# ESP_SCH.net
KiCad netlist of a schematic drawn in Altium Designer
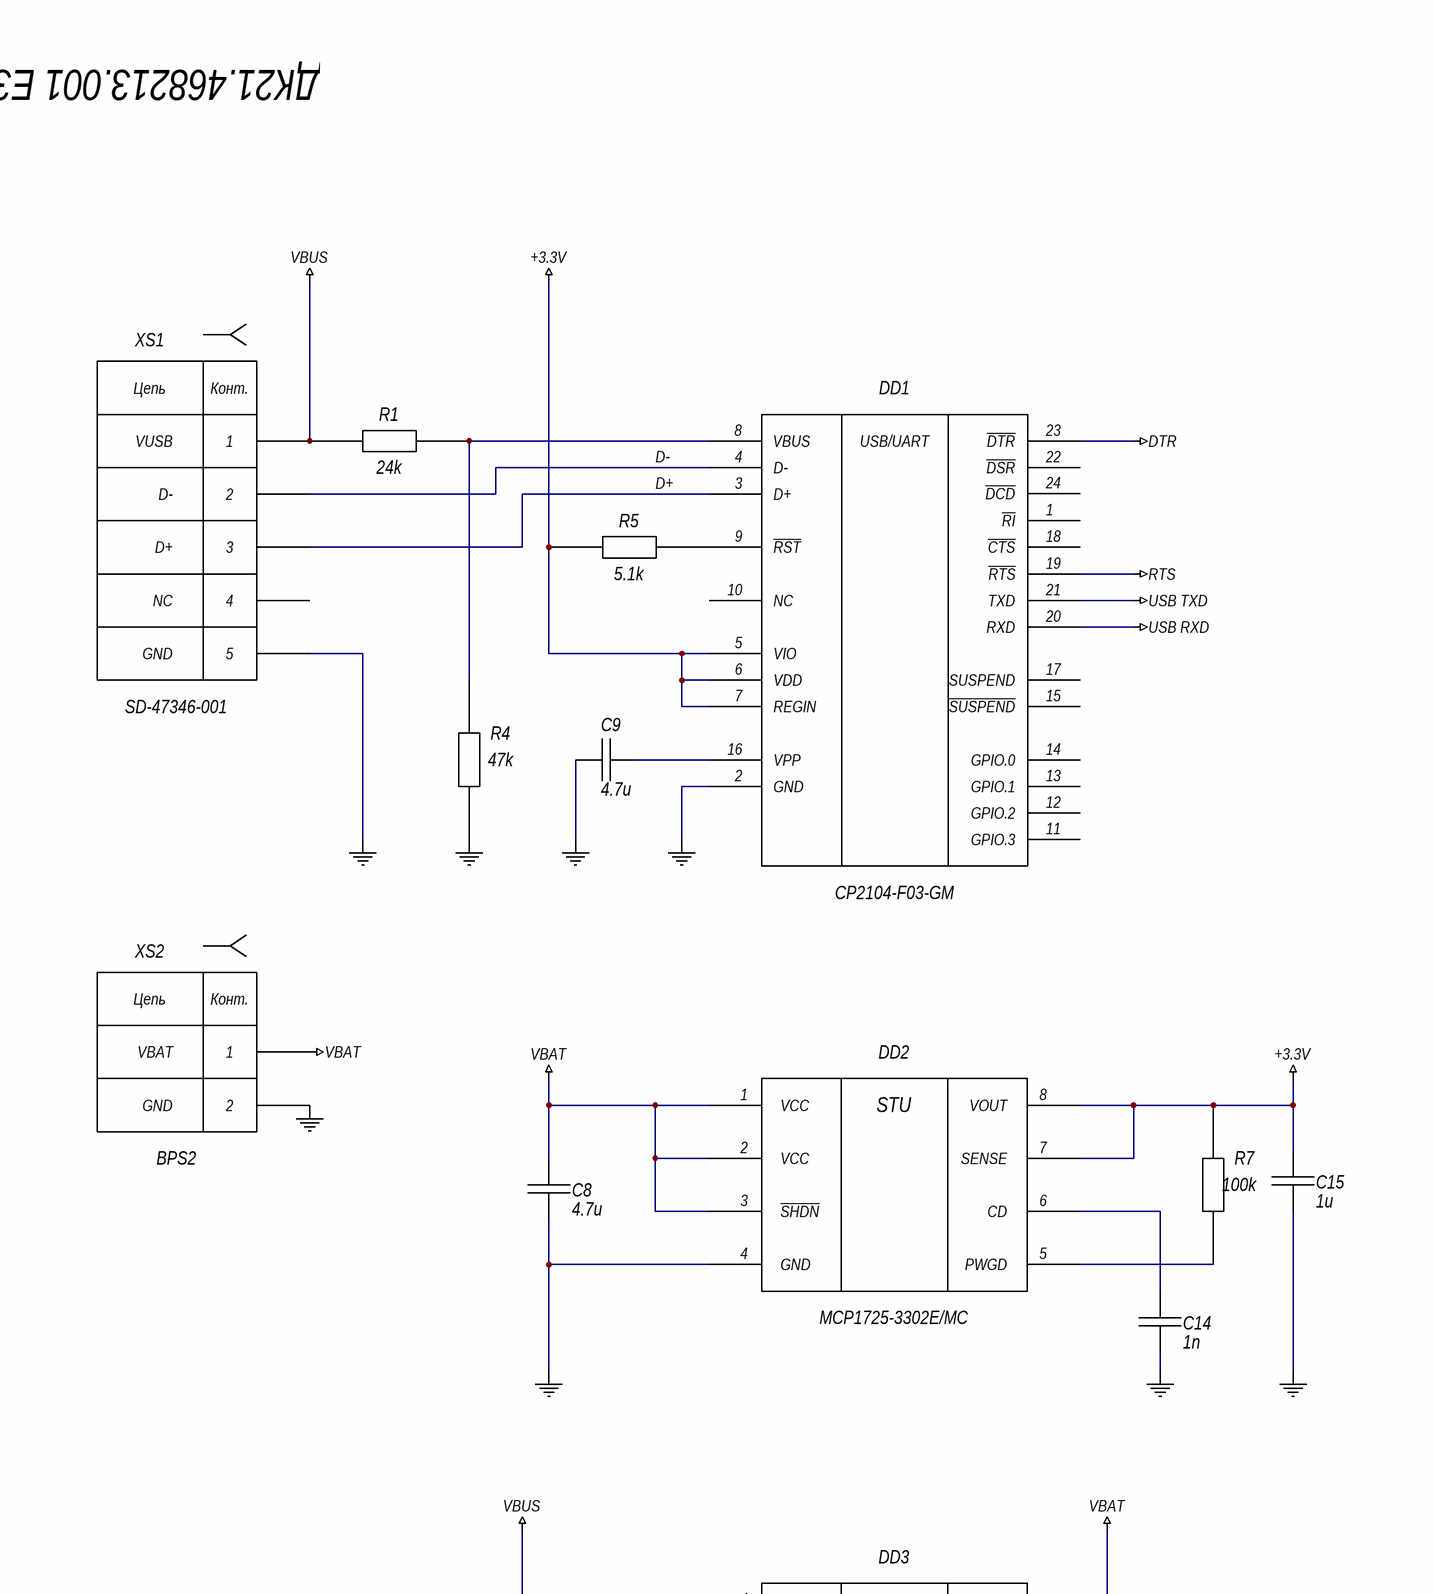
[diagram p0: ESP_SCH.SchDoc, top left]
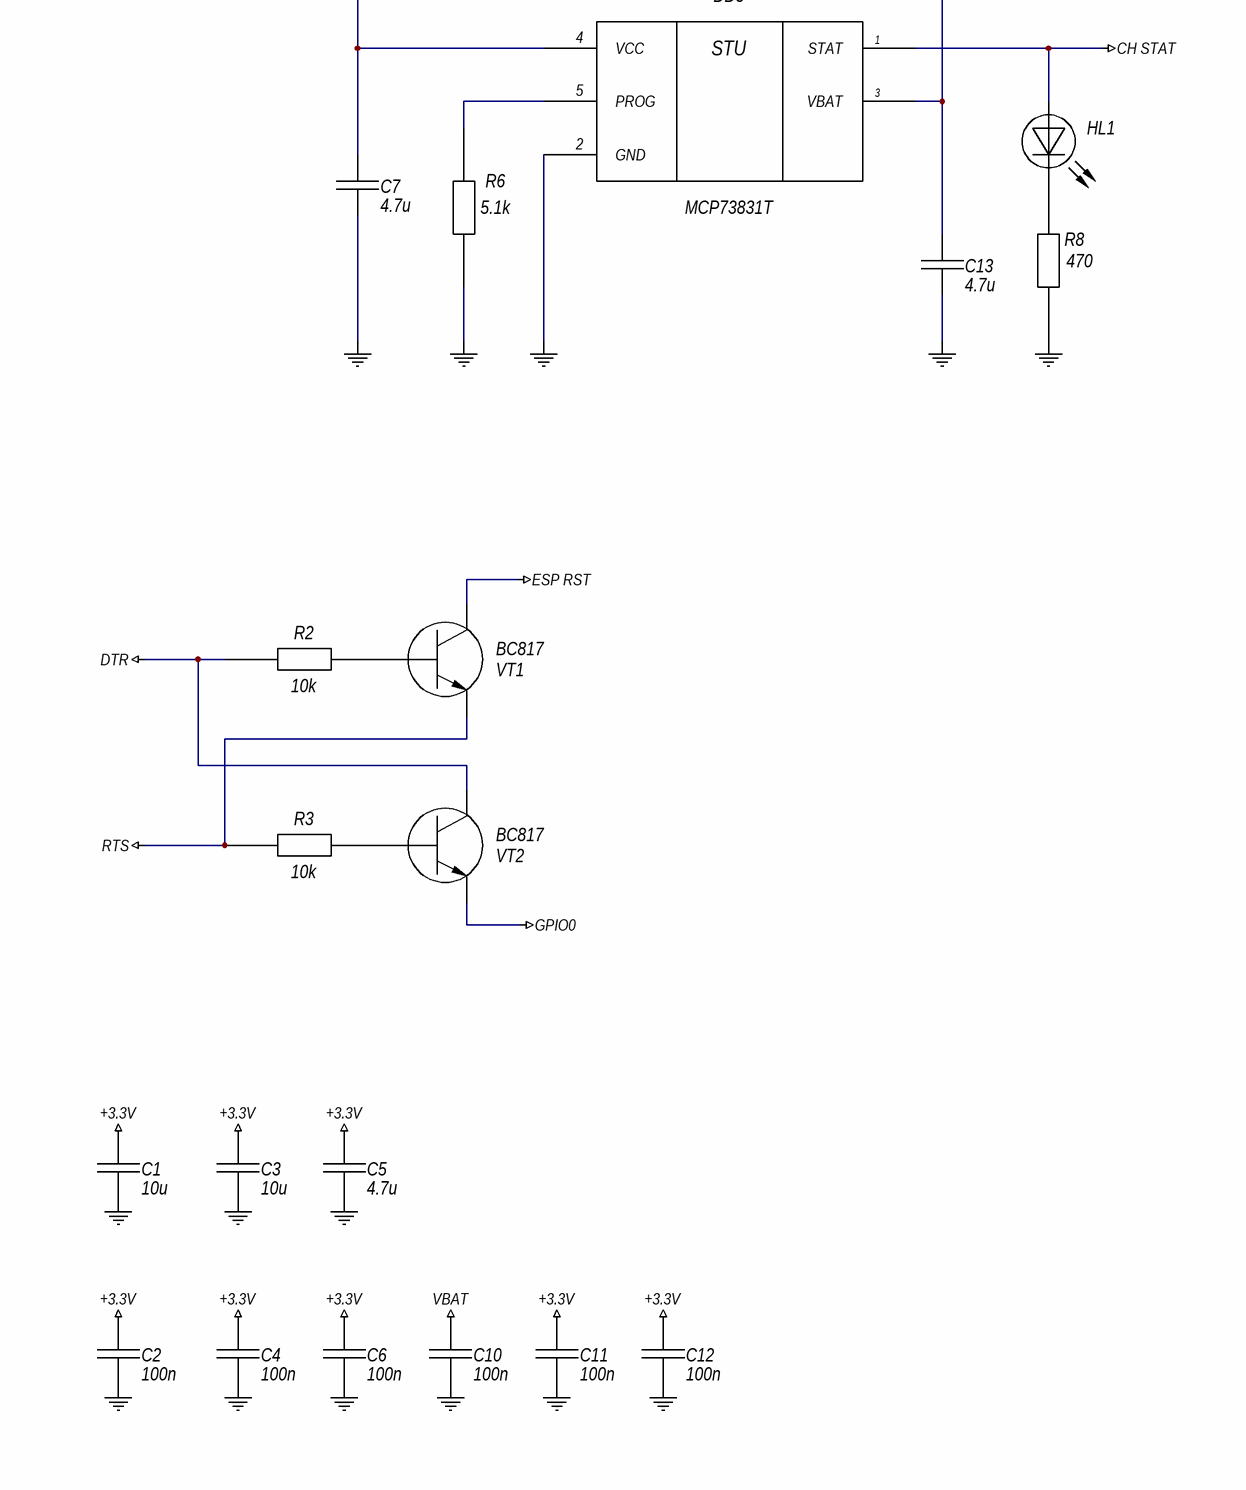
[diagram p1: ESP_SCH.SchDoc, bottom left]
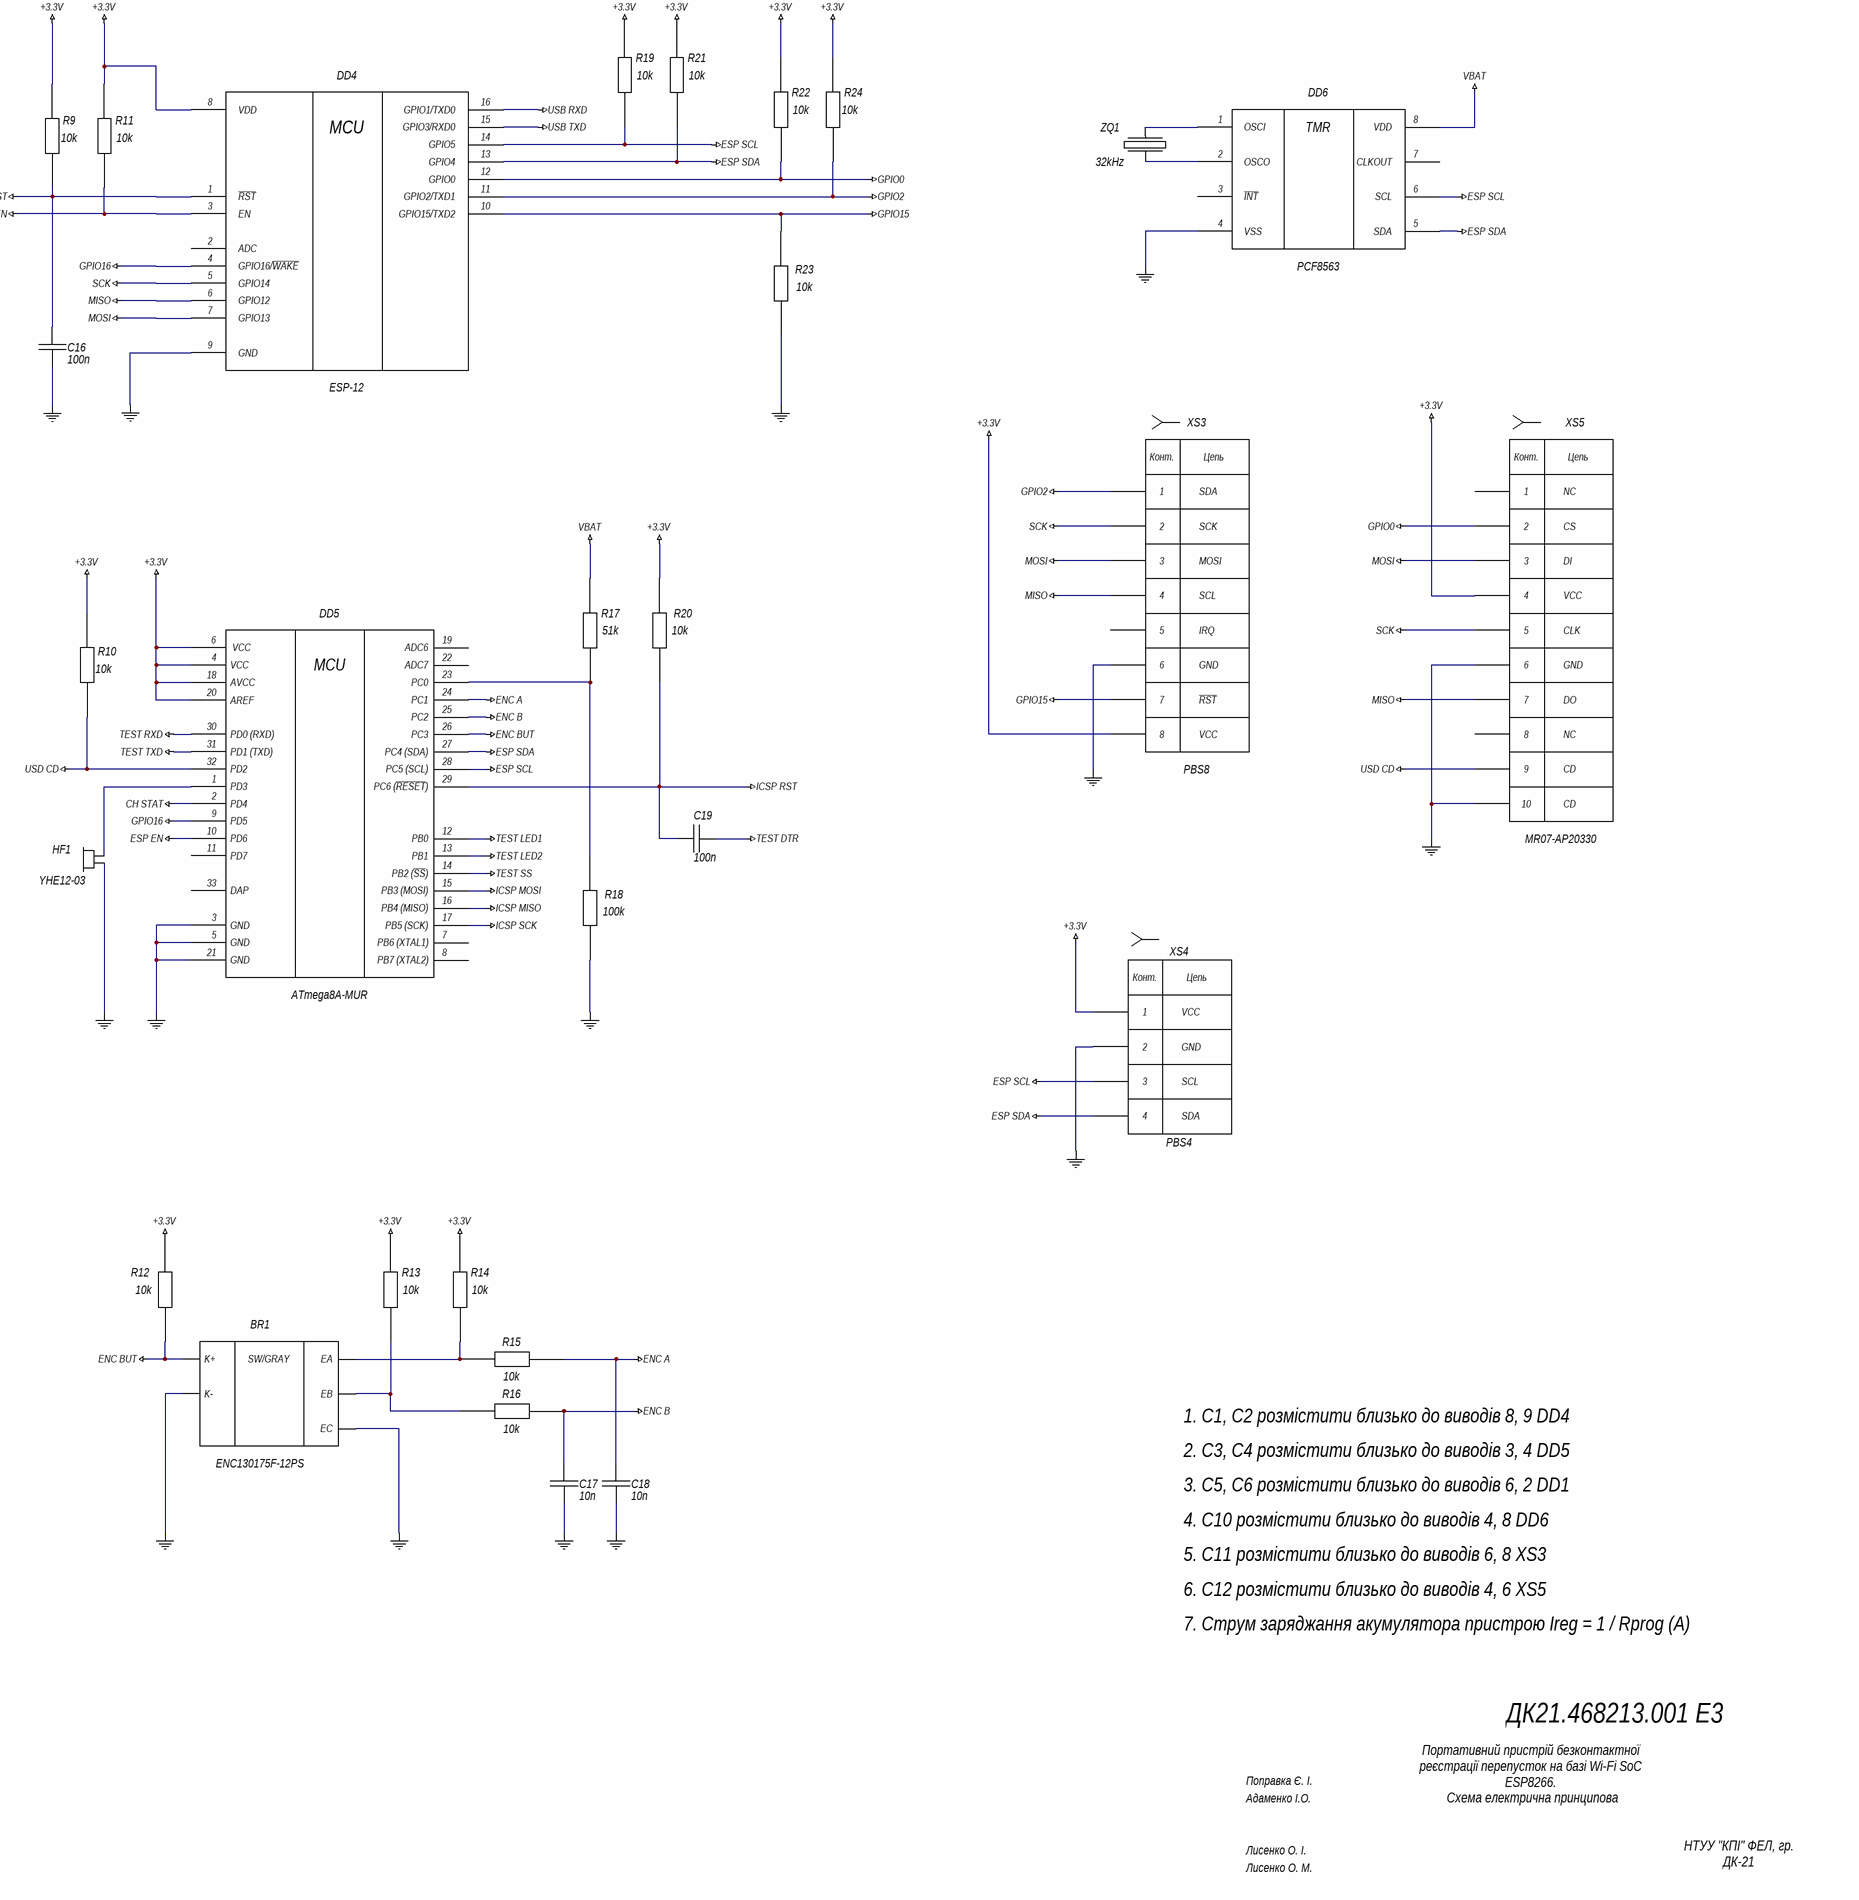
[diagram p2: ESP_SCH.SchDoc, bottom right]

(export (version "E")
  (design (tool "Eeschema 10.0.6"))
  (components
    (comp (ref "BR1")
      (value "ENC130175F-12PS")
      (footprint "ENCODER_LED_2")
      (libsource (lib "Symbols GOST") (part "ENC130175F-12PS"))
    )
    (comp (ref "C1")
      (value "10u")
      (footprint "RES0603")
      (description "Chip capasitor")
      (fields (field (name "PART NUMBER") "GRJ32ER71H475KE11") (field (name "VOLTAGE") "50V"))
      (libsource (lib "Symbols GOST") (part "C0805"))
    )
    (comp (ref "C2")
      (value "100n")
      (footprint "RES0603")
      (description "Chip capasitor")
      (fields (field (name "PART NUMBER") "GRJ32ER71H475KE11") (field (name "VOLTAGE") "50V"))
      (libsource (lib "Symbols GOST") (part "C0805"))
    )
    (comp (ref "C3")
      (value "10u")
      (footprint "RES0603")
      (description "Chip capasitor")
      (fields (field (name "PART NUMBER") "GRJ32ER71H475KE11") (field (name "VOLTAGE") "50V"))
      (libsource (lib "Symbols GOST") (part "C0805"))
    )
    (comp (ref "C4")
      (value "100n")
      (footprint "RES0603")
      (description "Chip capasitor")
      (fields (field (name "PART NUMBER") "GRJ32ER71H475KE11") (field (name "VOLTAGE") "50V"))
      (libsource (lib "Symbols GOST") (part "C0805"))
    )
    (comp (ref "C5")
      (value "4.7u")
      (footprint "RES0603")
      (description "Chip capasitor")
      (fields (field (name "PART NUMBER") "GRJ32ER71H475KE11") (field (name "VOLTAGE") "50V"))
      (libsource (lib "Symbols GOST") (part "C0805"))
    )
    (comp (ref "C6")
      (value "100n")
      (footprint "RES0603")
      (description "Chip capasitor")
      (fields (field (name "PART NUMBER") "GRJ32ER71H475KE11") (field (name "VOLTAGE") "50V"))
      (libsource (lib "Symbols GOST") (part "C0805"))
    )
    (comp (ref "C7")
      (value "4.7u")
      (footprint "RES0603")
      (description "Chip capasitor")
      (fields (field (name "PART NUMBER") "GRJ32ER71H475KE11") (field (name "VOLTAGE") "50V"))
      (libsource (lib "Symbols GOST") (part "C0805"))
    )
    (comp (ref "C8")
      (value "4.7u")
      (footprint "RES0603")
      (description "Chip capasitor")
      (fields (field (name "PART NUMBER") "GRJ32ER71H475KE11") (field (name "VOLTAGE") "50V"))
      (libsource (lib "Symbols GOST") (part "C0805"))
    )
    (comp (ref "C9")
      (value "4.7u")
      (footprint "RES0603")
      (description "Chip capasitor")
      (fields (field (name "PART NUMBER") "GRJ32ER71H475KE11") (field (name "VOLTAGE") "50V"))
      (libsource (lib "Symbols GOST") (part "C0805"))
    )
    (comp (ref "C10")
      (value "100n")
      (footprint "RES0603")
      (description "Chip capasitor")
      (fields (field (name "PART NUMBER") "GRJ32ER71H475KE11") (field (name "VOLTAGE") "50V"))
      (libsource (lib "Symbols GOST") (part "C0805"))
    )
    (comp (ref "C11")
      (value "100n")
      (footprint "RES0603")
      (description "Chip capasitor")
      (fields (field (name "PART NUMBER") "GRJ32ER71H475KE11") (field (name "VOLTAGE") "50V"))
      (libsource (lib "Symbols GOST") (part "C0805"))
    )
    (comp (ref "C12")
      (value "100n")
      (footprint "RES0603")
      (description "Chip capasitor")
      (fields (field (name "PART NUMBER") "GRJ32ER71H475KE11") (field (name "VOLTAGE") "50V"))
      (libsource (lib "Symbols GOST") (part "C0805"))
    )
    (comp (ref "C13")
      (value "4.7u")
      (footprint "RES0603")
      (description "Chip capasitor")
      (fields (field (name "PART NUMBER") "GRJ32ER71H475KE11") (field (name "VOLTAGE") "50V"))
      (libsource (lib "Symbols GOST") (part "C0805"))
    )
    (comp (ref "C14")
      (value "1n")
      (footprint "RES0603")
      (description "Chip capasitor")
      (fields (field (name "PART NUMBER") "GRJ32ER71H475KE11") (field (name "VOLTAGE") "50V"))
      (libsource (lib "Symbols GOST") (part "C0805"))
    )
    (comp (ref "C15")
      (value "1u")
      (footprint "RES0603")
      (description "Chip capasitor")
      (fields (field (name "PART NUMBER") "GRJ32ER71H475KE11") (field (name "VOLTAGE") "50V"))
      (libsource (lib "Symbols GOST") (part "C0805"))
    )
    (comp (ref "C16")
      (value "100n")
      (footprint "RES0603")
      (description "Chip capasitor")
      (fields (field (name "PART NUMBER") "GRJ32ER71H475KE11") (field (name "VOLTAGE") "50V"))
      (libsource (lib "Symbols GOST") (part "C0805"))
    )
    (comp (ref "C17")
      (value "10n")
      (footprint "RES0603")
      (description "Chip capasitor")
      (fields (field (name "PART NUMBER") "GRJ32ER71H475KE11") (field (name "VOLTAGE") "50V"))
      (libsource (lib "Symbols GOST") (part "C0805"))
    )
    (comp (ref "C18")
      (value "10n")
      (footprint "RES0603")
      (description "Chip capasitor")
      (fields (field (name "PART NUMBER") "GRJ32ER71H475KE11") (field (name "VOLTAGE") "50V"))
      (libsource (lib "Symbols GOST") (part "C0805"))
    )
    (comp (ref "C19")
      (value "100n")
      (footprint "RES0603")
      (description "Chip capasitor")
      (fields (field (name "PART NUMBER") "GRJ32ER71H475KE11") (field (name "VOLTAGE") "50V"))
      (libsource (lib "Symbols GOST") (part "C0805"))
    )
    (comp (ref "DD1")
      (value "CP2104-F03-GM")
      (footprint "SLAB-QFN-24-2675x2675TP_M")
      (fields (field (name "MANUFACTURER") "Silicon Labs"))
      (libsource (lib "Symbols GOST") (part "CP2104-F03-GM"))
    )
    (comp (ref "DD2")
      (value "MCP1725-3302E/MC")
      (footprint "SOIC127P600X175-8N")
      (description "MCP1725-3302E/MC ULDO")
      (libsource (lib "Symbols GOST") (part "MCP1725-3302E/MC"))
    )
    (comp (ref "DD3")
      (value "MCP73831T")
      (footprint "SOT95P270X145-5N")
      (description "MCP73831T Li-ion/Li-po charger")
      (fields (field (name "PART NUMBER") "MCP73831/2  SOT-23-5"))
      (libsource (lib "Symbols GOST") (part "MCP73831T"))
    )
    (comp (ref "DD4")
      (value "ESP-12")
      (footprint "ESP_12_E")
      (description "ESP-12 Wi-Fi Module")
      (libsource (lib "Symbols GOST") (part "ESP-12E"))
    )
    (comp (ref "DD5")
      (value "ATmega8A-MUR")
      (footprint "QFN127P600-8N")
      (libsource (lib "Symbols GOST") (part "ATmega8A-MUR"))
    )
    (comp (ref "DD6")
      (value "PCF8563")
      (footprint "SOIC8")
      (fields (field (name "PART NUMBER") "MCP1725-3302E/MC"))
      (libsource (lib "Symbols GOST") (part "PCF8563"))
    )
    (comp (ref "HF1")
      (value "YHE12-03")
      (footprint "PCBComponent_1")
      (description "Пьезоизлучатель")
      (libsource (lib "Symbols GOST") (part "HF"))
    )
    (comp (ref "HL1")
      (value "~")
      (footprint "RES0603")
      (description "Светодиод")
      (fields (field (name "PART NUMBER") "KP-2012VGC-A"))
      (libsource (lib "Symbols GOST") (part "HL_02"))
    )
    (comp (ref "R1")
      (value "24k")
      (footprint "RES0603")
      (description "Резистор")
      (fields (field (name "PART NUMBER") "RC0805JR-070RL") (field (name "VOLTAGE") "150V"))
      (libsource (lib "") (part "R0805_3"))
    )
    (comp (ref "R2")
      (value "10k")
      (footprint "RES0603")
      (description "Резистор")
      (fields (field (name "PART NUMBER") "RC0805JR-070RL") (field (name "VOLTAGE") "150V"))
      (libsource (lib "") (part "R0805_2"))
    )
    (comp (ref "R3")
      (value "10k")
      (footprint "RES0603")
      (description "Резистор")
      (fields (field (name "PART NUMBER") "RC0805JR-070RL") (field (name "VOLTAGE") "150V"))
      (libsource (lib "") (part "R0805_2"))
    )
    (comp (ref "R4")
      (value "47k")
      (footprint "RES0603")
      (description "Резистор")
      (fields (field (name "PART NUMBER") "RC0805JR-070RL") (field (name "VOLTAGE") "150V"))
      (libsource (lib "Symbols GOST") (part "R0805"))
    )
    (comp (ref "R5")
      (value "5.1k")
      (footprint "RES0603")
      (description "Резистор")
      (fields (field (name "PART NUMBER") "RC0805JR-070RL") (field (name "VOLTAGE") "150V"))
      (libsource (lib "") (part "R0805_1"))
    )
    (comp (ref "R6")
      (value "5.1k")
      (footprint "RES0603")
      (description "Резистор")
      (fields (field (name "PART NUMBER") "RC0805JR-070RL") (field (name "VOLTAGE") "150V"))
      (libsource (lib "Symbols GOST") (part "R0805"))
    )
    (comp (ref "R7")
      (value "100k")
      (footprint "RES0603")
      (description "Резистор")
      (fields (field (name "PART NUMBER") "RC0805JR-070RL") (field (name "VOLTAGE") "150V"))
      (libsource (lib "Symbols GOST") (part "R0805"))
    )
    (comp (ref "R8")
      (value "470")
      (footprint "RES0603")
      (description "Резистор")
      (fields (field (name "PART NUMBER") "RC0805JR-070RL") (field (name "VOLTAGE") "150V"))
      (libsource (lib "Symbols GOST") (part "R0805"))
    )
    (comp (ref "R9")
      (value "10k")
      (footprint "RES0603")
      (description "Резистор")
      (fields (field (name "PART NUMBER") "RC0805JR-070RL") (field (name "VOLTAGE") "150V"))
      (libsource (lib "Symbols GOST") (part "R0805"))
    )
    (comp (ref "R10")
      (value "10k")
      (footprint "RES0603")
      (description "Резистор")
      (fields (field (name "PART NUMBER") "RC0805JR-070RL") (field (name "VOLTAGE") "150V"))
      (libsource (lib "Symbols GOST") (part "R0805"))
    )
    (comp (ref "R11")
      (value "10k")
      (footprint "RES0603")
      (description "Резистор")
      (fields (field (name "PART NUMBER") "RC0805JR-070RL") (field (name "VOLTAGE") "150V"))
      (libsource (lib "Symbols GOST") (part "R0805"))
    )
    (comp (ref "R12")
      (value "10k")
      (footprint "RES0603")
      (description "Резистор")
      (fields (field (name "PART NUMBER") "RC0805JR-070RL") (field (name "VOLTAGE") "150V"))
      (libsource (lib "") (part "R0805_1"))
    )
    (comp (ref "R13")
      (value "10k")
      (footprint "RES0603")
      (description "Резистор")
      (fields (field (name "PART NUMBER") "RC0805JR-070RL") (field (name "VOLTAGE") "150V"))
      (libsource (lib "Symbols GOST") (part "R0805"))
    )
    (comp (ref "R14")
      (value "10k")
      (footprint "RES0603")
      (description "Резистор")
      (fields (field (name "PART NUMBER") "RC0805JR-070RL") (field (name "VOLTAGE") "150V"))
      (libsource (lib "Symbols GOST") (part "R0805"))
    )
    (comp (ref "R15")
      (value "10k")
      (footprint "RES0603")
      (description "Резистор")
      (fields (field (name "PART NUMBER") "RC0805JR-070RL") (field (name "VOLTAGE") "150V"))
      (libsource (lib "") (part "R0805_1"))
    )
    (comp (ref "R16")
      (value "10k")
      (footprint "RES0603")
      (description "Резистор")
      (fields (field (name "PART NUMBER") "RC0805JR-070RL") (field (name "VOLTAGE") "150V"))
      (libsource (lib "") (part "R0805_1"))
    )
    (comp (ref "R17")
      (value "51k")
      (footprint "RES0603")
      (description "Резистор")
      (fields (field (name "PART NUMBER") "RC0805JR-070RL") (field (name "VOLTAGE") "150V"))
      (libsource (lib "Symbols GOST") (part "R0805"))
    )
    (comp (ref "R18")
      (value "100k")
      (footprint "RES0603")
      (description "Резистор")
      (fields (field (name "PART NUMBER") "RC0805JR-070RL") (field (name "VOLTAGE") "150V"))
      (libsource (lib "Symbols GOST") (part "R0805"))
    )
    (comp (ref "R19")
      (value "10k")
      (footprint "RES0603")
      (description "Резистор")
      (fields (field (name "PART NUMBER") "RC0805JR-070RL") (field (name "VOLTAGE") "150V"))
      (libsource (lib "Symbols GOST") (part "R0805"))
    )
    (comp (ref "R20")
      (value "10k")
      (footprint "RES0603")
      (description "Резистор")
      (fields (field (name "PART NUMBER") "RC0805JR-070RL") (field (name "VOLTAGE") "150V"))
      (libsource (lib "Symbols GOST") (part "R0805"))
    )
    (comp (ref "R21")
      (value "10k")
      (footprint "RES0603")
      (description "Резистор")
      (fields (field (name "PART NUMBER") "RC0805JR-070RL") (field (name "VOLTAGE") "150V"))
      (libsource (lib "Symbols GOST") (part "R0805"))
    )
    (comp (ref "R22")
      (value "10k")
      (footprint "RES0603")
      (description "Резистор")
      (fields (field (name "PART NUMBER") "RC0805JR-070RL") (field (name "VOLTAGE") "150V"))
      (libsource (lib "Symbols GOST") (part "R0805"))
    )
    (comp (ref "R23")
      (value "10k")
      (footprint "RES0603")
      (description "Резистор")
      (fields (field (name "PART NUMBER") "RC0805JR-070RL") (field (name "VOLTAGE") "150V"))
      (libsource (lib "Symbols GOST") (part "R0805"))
    )
    (comp (ref "R24")
      (value "10k")
      (footprint "RES0603")
      (description "Резистор")
      (fields (field (name "PART NUMBER") "RC0805JR-070RL") (field (name "VOLTAGE") "150V"))
      (libsource (lib "Symbols GOST") (part "R0805"))
    )
    (comp (ref "VT1")
      (value "BC817")
      (footprint "SOT95P245X110-3N")
      (description "Транзистор биполярный, NPN")
      (libsource (lib "Symbols GOST") (part "VT_01"))
    )
    (comp (ref "VT2")
      (value "BC817")
      (footprint "SOT95P245X110-3N")
      (description "Транзистор биполярный, NPN")
      (libsource (lib "Symbols GOST") (part "VT_01"))
    )
    (comp (ref "XS1")
      (value "SD-47346-001")
      (footprint "USB-MICROB")
      (description "micro USB")
      (fields (field (name "PART NUMBER") "RFID-RC522 MFRC522 модуль"))
      (libsource (lib "Symbols GOST") (part "usb"))
    )
    (comp (ref "XS2")
      (value "BPS2")
      (footprint "PCBComponent_1 - duplicate")
      (description "battery")
      (fields (field (name "PART NUMBER") "RFID-RC522 MFRC522 модуль"))
      (libsource (lib "Symbols GOST") (part "lipo"))
    )
    (comp (ref "XS3")
      (value "PBS8")
      (footprint "RFID-RC522")
      (description "RC522 RFID module")
      (fields (field (name "PART NUMBER") "RFID-RC522 MFRC522 модуль"))
      (libsource (lib "Symbols GOST") (part "RC522"))
    )
    (comp (ref "XS4")
      (value "PBS4")
      (footprint "SSD")
      (description "SSD1306 OLED Screen Module")
      (fields (field (name "PART NUMBER") "RFID-RC522 MFRC522 модуль"))
      (libsource (lib "Symbols GOST") (part "SSD1306"))
    )
    (comp (ref "XS5")
      (value "MR07-AP20330")
      (footprint "MICROSD Slot")
      (description "RC522 RFID module")
      (fields (field (name "PART NUMBER") "RFID-RC522 MFRC522 модуль"))
      (libsource (lib "Symbols GOST") (part "uSD"))
    )
    (comp (ref "ZQ1")
      (value "32kHz")
      (footprint "PCBComponent_1 - duplicate1")
      (description "Элемент пьезоэлектрический с двумя выводами")
      (fields (field (name "PART NUMBER") "HC49/US 16MHz"))
      (libsource (lib "Symbols GOST") (part "ZQ_01"))
    )
  )
  (nets
    (net (code "1") (name "+3.3V") (class "Default")
      (node (ref "C1") (pin "1") (pinfunction "1_1") (pintype "passive"))
      (node (ref "C11") (pin "1") (pinfunction "1_1") (pintype "passive"))
      (node (ref "C12") (pin "1") (pinfunction "1_1") (pintype "passive"))
      (node (ref "C15") (pin "1") (pinfunction "1_1") (pintype "passive"))
      (node (ref "C2") (pin "1") (pinfunction "1_1") (pintype "passive"))
      (node (ref "C3") (pin "1") (pinfunction "1_1") (pintype "passive"))
      (node (ref "C4") (pin "1") (pinfunction "1_1") (pintype "passive"))
      (node (ref "C5") (pin "1") (pinfunction "1_1") (pintype "passive"))
      (node (ref "C6") (pin "1") (pinfunction "1_1") (pintype "passive"))
      (node (ref "DD1") (pin "5") (pinfunction "VIO_5") (pintype "passive"))
      (node (ref "DD1") (pin "6") (pinfunction "VDD_6") (pintype "passive"))
      (node (ref "DD1") (pin "7") (pinfunction "REGIN_7") (pintype "passive"))
      (node (ref "DD2") (pin "7") (pinfunction "SENSE_7") (pintype "passive"))
      (node (ref "DD2") (pin "8") (pinfunction "VOUT_8") (pintype "passive"))
      (node (ref "DD4") (pin "8") (pinfunction "VDD_8") (pintype "passive"))
      (node (ref "DD5") (pin "18") (pinfunction "AVCC_18") (pintype "passive"))
      (node (ref "DD5") (pin "20") (pinfunction "AREF_20") (pintype "passive"))
      (node (ref "DD5") (pin "4") (pinfunction "VCC_4") (pintype "passive"))
      (node (ref "DD5") (pin "6") (pinfunction "VCC_6") (pintype "passive"))
      (node (ref "R10") (pin "2") (pinfunction "Terminal_B_2") (pintype "passive"))
      (node (ref "R11") (pin "2") (pinfunction "Terminal_B_2") (pintype "passive"))
      (node (ref "R12") (pin "2") (pinfunction "Terminal_B_2") (pintype "passive"))
      (node (ref "R13") (pin "2") (pinfunction "Terminal_B_2") (pintype "passive"))
      (node (ref "R14") (pin "2") (pinfunction "Terminal_B_2") (pintype "passive"))
      (node (ref "R19") (pin "2") (pinfunction "Terminal_B_2") (pintype "passive"))
      (node (ref "R20") (pin "2") (pinfunction "Terminal_B_2") (pintype "passive"))
      (node (ref "R21") (pin "2") (pinfunction "Terminal_B_2") (pintype "passive"))
      (node (ref "R22") (pin "2") (pinfunction "Terminal_B_2") (pintype "passive"))
      (node (ref "R24") (pin "2") (pinfunction "Terminal_B_2") (pintype "passive"))
      (node (ref "R5") (pin "1") (pinfunction "Terminal_A_1") (pintype "passive"))
      (node (ref "R7") (pin "2") (pinfunction "Terminal_B_2") (pintype "passive"))
      (node (ref "R9") (pin "2") (pinfunction "Terminal_B_2") (pintype "passive"))
      (node (ref "XS3") (pin "8") (pinfunction "VCC_8") (pintype "passive"))
      (node (ref "XS4") (pin "1") (pinfunction "VCC_1") (pintype "passive"))
      (node (ref "XS5") (pin "4") (pinfunction "VCC_4") (pintype "passive"))
    )
    (net (code "2") (name "/D+") (class "Default")
      (node (ref "DD1") (pin "3") (pinfunction "D+_3") (pintype "passive"))
      (node (ref "XS1") (pin "3") (pinfunction "D+_3") (pintype "passive"))
    )
    (net (code "3") (name "/D-") (class "Default")
      (node (ref "DD1") (pin "4") (pinfunction "D-_4") (pintype "passive"))
      (node (ref "XS1") (pin "2") (pinfunction "D-_2") (pintype "passive"))
    )
    (net (code "4") (name "CH STAT") (class "Default")
      (node (ref "DD3") (pin "1") (pinfunction "STAT_1") (pintype "passive"))
      (node (ref "DD5") (pin "2") (pinfunction "PD4_2") (pintype "passive"))
      (node (ref "HL1") (pin "1") (pinfunction "A_1") (pintype "passive"))
    )
    (net (code "5") (name "DTR") (class "Default")
      (node (ref "DD1") (pin "23") (pinfunction "~{DTR}_23") (pintype "passive"))
      (node (ref "R2") (pin "2") (pinfunction "Terminal_B_2") (pintype "passive"))
      (node (ref "VT2") (pin "3") (pinfunction "K_3") (pintype "passive"))
    )
    (net (code "6") (name "ENC A") (class "Default")
      (node (ref "C18") (pin "1") (pinfunction "1_1") (pintype "passive"))
      (node (ref "DD5") (pin "24") (pinfunction "PC1_24") (pintype "passive"))
      (node (ref "R15") (pin "2") (pinfunction "Terminal_B_2") (pintype "passive"))
    )
    (net (code "7") (name "ENC B") (class "Default")
      (node (ref "C17") (pin "1") (pinfunction "1_1") (pintype "passive"))
      (node (ref "DD5") (pin "25") (pinfunction "PC2_25") (pintype "passive"))
      (node (ref "R16") (pin "2") (pinfunction "Terminal_B_2") (pintype "passive"))
    )
    (net (code "8") (name "ENC BUT") (class "Default")
      (node (ref "BR1") (pin "K+") (pinfunction "K+_K+") (pintype "passive"))
      (node (ref "DD5") (pin "26") (pinfunction "PC3_26") (pintype "passive"))
      (node (ref "R12") (pin "1") (pinfunction "Terminal_A_1") (pintype "passive"))
    )
    (net (code "9") (name "ESP EN") (class "Default")
      (node (ref "DD4") (pin "3") (pinfunction "EN_3") (pintype "passive"))
      (node (ref "DD5") (pin "10") (pinfunction "PD6_10") (pintype "passive"))
      (node (ref "R11") (pin "1") (pinfunction "Terminal_A_1") (pintype "passive"))
    )
    (net (code "10") (name "ESP RST") (class "Default")
      (node (ref "C16") (pin "1") (pinfunction "1_1") (pintype "passive"))
      (node (ref "DD4") (pin "1") (pinfunction "~{RST}_1") (pintype "passive"))
      (node (ref "R9") (pin "1") (pinfunction "Terminal_A_1") (pintype "passive"))
      (node (ref "VT1") (pin "3") (pinfunction "K_3") (pintype "passive"))
    )
    (net (code "11") (name "ESP SCL") (class "Default")
      (node (ref "DD4") (pin "14") (pinfunction "GPIO5_14") (pintype "passive"))
      (node (ref "DD5") (pin "28") (pinfunction "PC5_(SCL)_28") (pintype "passive"))
      (node (ref "DD6") (pin "6") (pinfunction "SCL_6") (pintype "passive"))
      (node (ref "R19") (pin "1") (pinfunction "Terminal_A_1") (pintype "passive"))
      (node (ref "XS4") (pin "3") (pinfunction "SCL_3") (pintype "passive"))
    )
    (net (code "12") (name "ESP SDA") (class "Default")
      (node (ref "DD4") (pin "13") (pinfunction "GPIO4_13") (pintype "passive"))
      (node (ref "DD5") (pin "27") (pinfunction "PC4_(SDA)_27") (pintype "passive"))
      (node (ref "DD6") (pin "5") (pinfunction "SDA_5") (pintype "passive"))
      (node (ref "R21") (pin "1") (pinfunction "Terminal_A_1") (pintype "passive"))
      (node (ref "XS4") (pin "4") (pinfunction "SDA_4") (pintype "passive"))
    )
    (net (code "13") (name "GND") (class "Default")
      (node (ref "BR1") (pin "EC") (pinfunction "EC_EC") (pintype "passive"))
      (node (ref "BR1") (pin "K-") (pinfunction "K-_K-") (pintype "passive"))
      (node (ref "C1") (pin "2") (pinfunction "2_2") (pintype "passive"))
      (node (ref "C10") (pin "2") (pinfunction "2_2") (pintype "passive"))
      (node (ref "C11") (pin "2") (pinfunction "2_2") (pintype "passive"))
      (node (ref "C12") (pin "2") (pinfunction "2_2") (pintype "passive"))
      (node (ref "C13") (pin "2") (pinfunction "2_2") (pintype "passive"))
      (node (ref "C14") (pin "2") (pinfunction "2_2") (pintype "passive"))
      (node (ref "C15") (pin "2") (pinfunction "2_2") (pintype "passive"))
      (node (ref "C16") (pin "2") (pinfunction "2_2") (pintype "passive"))
      (node (ref "C17") (pin "2") (pinfunction "2_2") (pintype "passive"))
      (node (ref "C18") (pin "2") (pinfunction "2_2") (pintype "passive"))
      (node (ref "C2") (pin "2") (pinfunction "2_2") (pintype "passive"))
      (node (ref "C3") (pin "2") (pinfunction "2_2") (pintype "passive"))
      (node (ref "C4") (pin "2") (pinfunction "2_2") (pintype "passive"))
      (node (ref "C5") (pin "2") (pinfunction "2_2") (pintype "passive"))
      (node (ref "C6") (pin "2") (pinfunction "2_2") (pintype "passive"))
      (node (ref "C7") (pin "2") (pinfunction "2_2") (pintype "passive"))
      (node (ref "C8") (pin "2") (pinfunction "2_2") (pintype "passive"))
      (node (ref "C9") (pin "2") (pinfunction "2_2") (pintype "passive"))
      (node (ref "DD1") (pin "2") (pinfunction "GND_2") (pintype "passive"))
      (node (ref "DD2") (pin "4") (pinfunction "GND_4") (pintype "passive"))
      (node (ref "DD3") (pin "2") (pinfunction "GND_2") (pintype "passive"))
      (node (ref "DD4") (pin "9") (pinfunction "GND_9") (pintype "passive"))
      (node (ref "DD5") (pin "21") (pinfunction "GND_21") (pintype "passive"))
      (node (ref "DD5") (pin "3") (pinfunction "GND_3") (pintype "passive"))
      (node (ref "DD5") (pin "5") (pinfunction "GND_5") (pintype "passive"))
      (node (ref "DD6") (pin "4") (pinfunction "VSS_4") (pintype "passive"))
      (node (ref "HF1") (pin "1") (pinfunction "Terminal_A_1") (pintype "passive"))
      (node (ref "R18") (pin "1") (pinfunction "Terminal_A_1") (pintype "passive"))
      (node (ref "R23") (pin "1") (pinfunction "Terminal_A_1") (pintype "passive"))
      (node (ref "R4") (pin "1") (pinfunction "Terminal_A_1") (pintype "passive"))
      (node (ref "R6") (pin "1") (pinfunction "Terminal_A_1") (pintype "passive"))
      (node (ref "R8") (pin "1") (pinfunction "Terminal_A_1") (pintype "passive"))
      (node (ref "XS1") (pin "5") (pinfunction "GND_5") (pintype "passive"))
      (node (ref "XS2") (pin "2") (pinfunction "GND_2") (pintype "passive"))
      (node (ref "XS3") (pin "6") (pinfunction "GND_6") (pintype "passive"))
      (node (ref "XS4") (pin "2") (pinfunction "GND_2") (pintype "passive"))
      (node (ref "XS5") (pin "10") (pinfunction "CD_10") (pintype "passive"))
      (node (ref "XS5") (pin "6") (pinfunction "GND_6") (pintype "passive"))
    )
    (net (code "14") (name "GPIO0") (class "Default")
      (node (ref "DD4") (pin "12") (pinfunction "GPIO0_12") (pintype "passive"))
      (node (ref "R22") (pin "1") (pinfunction "Terminal_A_1") (pintype "passive"))
      (node (ref "VT2") (pin "2") (pinfunction "E_2") (pintype "passive"))
      (node (ref "XS5") (pin "2") (pinfunction "CS_2") (pintype "passive"))
    )
    (net (code "15") (name "GPIO2") (class "Default")
      (node (ref "DD4") (pin "11") (pinfunction "GPIO2/TXD1_11") (pintype "passive"))
      (node (ref "R24") (pin "1") (pinfunction "Terminal_A_1") (pintype "passive"))
      (node (ref "XS3") (pin "1") (pinfunction "SDA_1") (pintype "passive"))
    )
    (net (code "16") (name "GPIO15") (class "Default")
      (node (ref "DD4") (pin "10") (pinfunction "GPIO15/TXD2_10") (pintype "passive"))
      (node (ref "R23") (pin "2") (pinfunction "Terminal_B_2") (pintype "passive"))
      (node (ref "XS3") (pin "7") (pinfunction "~{RST}_7") (pintype "passive"))
    )
    (net (code "17") (name "GPIO16") (class "Default")
      (node (ref "DD4") (pin "4") (pinfunction "GPIO16/~{WAKE}_4") (pintype "passive"))
      (node (ref "DD5") (pin "9") (pinfunction "PD5_9") (pintype "passive"))
    )
    (net (code "18") (name "ICSP MISO") (class "Default")
      (node (ref "DD5") (pin "16") (pinfunction "PB4_(MISO)_16") (pintype "passive"))
    )
    (net (code "19") (name "ICSP MOSI") (class "Default")
      (node (ref "DD5") (pin "15") (pinfunction "PB3_(MOSI)_15") (pintype "passive"))
    )
    (net (code "20") (name "ICSP RST") (class "Default")
      (node (ref "C19") (pin "1") (pinfunction "1_1") (pintype "passive"))
      (node (ref "DD5") (pin "29") (pinfunction "PC6_(~{RESET})_29") (pintype "passive"))
      (node (ref "R20") (pin "1") (pinfunction "Terminal_A_1") (pintype "passive"))
    )
    (net (code "21") (name "ICSP SCK") (class "Default")
      (node (ref "DD5") (pin "17") (pinfunction "PB5_(SCK)_17") (pintype "passive"))
    )
    (net (code "22") (name "MISO") (class "Default")
      (node (ref "DD4") (pin "6") (pinfunction "GPIO12_6") (pintype "passive"))
      (node (ref "XS3") (pin "4") (pinfunction "SCL_4") (pintype "passive"))
      (node (ref "XS5") (pin "7") (pinfunction "DO_7") (pintype "passive"))
    )
    (net (code "23") (name "MOSI") (class "Default")
      (node (ref "DD4") (pin "7") (pinfunction "GPIO13_7") (pintype "passive"))
      (node (ref "XS3") (pin "3") (pinfunction "MOSI_3") (pintype "passive"))
      (node (ref "XS5") (pin "3") (pinfunction "DI_3") (pintype "passive"))
    )
    (net (code "24") (name "Net-(DD1-VBUS)") (class "Default")
      (node (ref "DD1") (pin "8") (pinfunction "VBUS_8") (pintype "passive"))
      (node (ref "R1") (pin "1") (pinfunction "Terminal_A_1") (pintype "passive"))
      (node (ref "R4") (pin "2") (pinfunction "Terminal_B_2") (pintype "passive"))
    )
    (net (code "25") (name "Net-(DD1-VPP)") (class "Default")
      (node (ref "C9") (pin "1") (pinfunction "1_1") (pintype "passive"))
      (node (ref "DD1") (pin "16") (pinfunction "VPP_16") (pintype "passive"))
    )
    (net (code "26") (name "Net-(DD1-~{RST})") (class "Default")
      (node (ref "DD1") (pin "9") (pinfunction "~{RST}_9") (pintype "passive"))
      (node (ref "R5") (pin "2") (pinfunction "Terminal_B_2") (pintype "passive"))
    )
    (net (code "27") (name "Net-(DD2-CD)") (class "Default")
      (node (ref "C14") (pin "1") (pinfunction "1_1") (pintype "passive"))
      (node (ref "DD2") (pin "6") (pinfunction "CD_6") (pintype "passive"))
    )
    (net (code "28") (name "Net-(DD2-PWGD)") (class "Default")
      (node (ref "DD2") (pin "5") (pinfunction "PWGD_5") (pintype "passive"))
      (node (ref "R7") (pin "1") (pinfunction "Terminal_A_1") (pintype "passive"))
    )
    (net (code "29") (name "Net-(DD3-PROG)") (class "Default")
      (node (ref "DD3") (pin "5") (pinfunction "PROG_5") (pintype "passive"))
      (node (ref "R6") (pin "2") (pinfunction "Terminal_B_2") (pintype "passive"))
    )
    (net (code "30") (name "Net-(DD5-PC0)") (class "Default")
      (node (ref "DD5") (pin "23") (pinfunction "PC0_23") (pintype "passive"))
      (node (ref "R17") (pin "1") (pinfunction "Terminal_A_1") (pintype "passive"))
      (node (ref "R18") (pin "2") (pinfunction "Terminal_B_2") (pintype "passive"))
    )
    (net (code "31") (name "Net-(DD5-PD3)") (class "Default")
      (node (ref "DD5") (pin "1") (pinfunction "PD3_1") (pintype "passive"))
      (node (ref "HF1") (pin "2") (pinfunction "Terminal_B_2") (pintype "passive"))
    )
    (net (code "32") (name "Net-(DD6-OSCI)") (class "Default")
      (node (ref "DD6") (pin "1") (pinfunction "OSCI_1") (pintype "passive"))
      (node (ref "ZQ1") (pin "1") (pintype "passive"))
    )
    (net (code "33") (name "Net-(DD6-OSCO)") (class "Default")
      (node (ref "DD6") (pin "2") (pinfunction "OSCO_2") (pintype "passive"))
      (node (ref "ZQ1") (pin "2") (pintype "passive"))
    )
    (net (code "34") (name "Net-(HL1-K)") (class "Default")
      (node (ref "HL1") (pin "2") (pinfunction "K_2") (pintype "passive"))
      (node (ref "R8") (pin "2") (pinfunction "Terminal_B_2") (pintype "passive"))
    )
    (net (code "35") (name "Net-(R2-Terminal_A)") (class "Default")
      (node (ref "R2") (pin "1") (pinfunction "Terminal_A_1") (pintype "passive"))
      (node (ref "VT1") (pin "1") (pinfunction "B_1") (pintype "passive"))
    )
    (net (code "36") (name "Net-(R3-Terminal_A)") (class "Default")
      (node (ref "R3") (pin "1") (pinfunction "Terminal_A_1") (pintype "passive"))
      (node (ref "VT2") (pin "1") (pinfunction "B_1") (pintype "passive"))
    )
    (net (code "37") (name "Net-(R13-Terminal_A)") (class "Default")
      (node (ref "BR1") (pin "EB") (pinfunction "EB_EB") (pintype "passive"))
      (node (ref "R13") (pin "1") (pinfunction "Terminal_A_1") (pintype "passive"))
      (node (ref "R16") (pin "1") (pinfunction "Terminal_A_1") (pintype "passive"))
    )
    (net (code "38") (name "Net-(R14-Terminal_A)") (class "Default")
      (node (ref "BR1") (pin "EA") (pinfunction "EA_EA") (pintype "passive"))
      (node (ref "R14") (pin "1") (pinfunction "Terminal_A_1") (pintype "passive"))
      (node (ref "R15") (pin "1") (pinfunction "Terminal_A_1") (pintype "passive"))
    )
    (net (code "39") (name "RTS") (class "Default")
      (node (ref "DD1") (pin "19") (pinfunction "~{RTS}_19") (pintype "passive"))
      (node (ref "R3") (pin "2") (pinfunction "Terminal_B_2") (pintype "passive"))
      (node (ref "VT1") (pin "2") (pinfunction "E_2") (pintype "passive"))
    )
    (net (code "40") (name "SCK") (class "Default")
      (node (ref "DD4") (pin "5") (pinfunction "GPIO14_5") (pintype "passive"))
      (node (ref "XS3") (pin "2") (pinfunction "SCK_2") (pintype "passive"))
      (node (ref "XS5") (pin "5") (pinfunction "CLK_5") (pintype "passive"))
    )
    (net (code "41") (name "TEST DTR") (class "Default")
      (node (ref "C19") (pin "2") (pinfunction "2_2") (pintype "passive"))
    )
    (net (code "42") (name "TEST LED1") (class "Default")
      (node (ref "DD5") (pin "12") (pinfunction "PB0_12") (pintype "passive"))
    )
    (net (code "43") (name "TEST LED2") (class "Default")
      (node (ref "DD5") (pin "13") (pinfunction "PB1_13") (pintype "passive"))
    )
    (net (code "44") (name "TEST RXD") (class "Default")
      (node (ref "DD5") (pin "30") (pinfunction "PD0_(RXD)_30") (pintype "passive"))
    )
    (net (code "45") (name "TEST SS") (class "Default")
      (node (ref "DD5") (pin "14") (pinfunction "PB2_(~{SS})_14") (pintype "passive"))
    )
    (net (code "46") (name "TEST TXD") (class "Default")
      (node (ref "DD5") (pin "31") (pinfunction "PD1_(TXD)_31") (pintype "passive"))
    )
    (net (code "47") (name "USB RXD") (class "Default")
      (node (ref "DD1") (pin "20") (pinfunction "RXD_20") (pintype "passive"))
      (node (ref "DD4") (pin "16") (pinfunction "GPIO1/TXD0_16") (pintype "passive"))
    )
    (net (code "48") (name "USB TXD") (class "Default")
      (node (ref "DD1") (pin "21") (pinfunction "TXD_21") (pintype "passive"))
      (node (ref "DD4") (pin "15") (pinfunction "GPIO3/RXD0_15") (pintype "passive"))
    )
    (net (code "49") (name "USD CD") (class "Default")
      (node (ref "DD5") (pin "32") (pinfunction "PD2_32") (pintype "passive"))
      (node (ref "R10") (pin "1") (pinfunction "Terminal_A_1") (pintype "passive"))
      (node (ref "XS5") (pin "9") (pinfunction "CD_9") (pintype "passive"))
    )
    (net (code "50") (name "VBAT") (class "Default")
      (node (ref "C10") (pin "1") (pinfunction "1_1") (pintype "passive"))
      (node (ref "C13") (pin "1") (pinfunction "1_1") (pintype "passive"))
      (node (ref "C8") (pin "1") (pinfunction "1_1") (pintype "passive"))
      (node (ref "DD2") (pin "1") (pinfunction "VCC_1") (pintype "passive"))
      (node (ref "DD2") (pin "2") (pinfunction "VCC_2") (pintype "passive"))
      (node (ref "DD2") (pin "3") (pinfunction "~{SHDN}_3") (pintype "passive"))
      (node (ref "DD3") (pin "3") (pinfunction "VBAT_3") (pintype "passive"))
      (node (ref "DD6") (pin "8") (pinfunction "VDD_8") (pintype "passive"))
      (node (ref "R17") (pin "2") (pinfunction "Terminal_B_2") (pintype "passive"))
      (node (ref "XS2") (pin "1") (pinfunction "VBAT_1") (pintype "passive"))
    )
    (net (code "51") (name "VBUS") (class "Default")
      (node (ref "C7") (pin "1") (pinfunction "1_1") (pintype "passive"))
      (node (ref "DD3") (pin "4") (pinfunction "VCC_4") (pintype "passive"))
      (node (ref "R1") (pin "2") (pinfunction "Terminal_B_2") (pintype "passive"))
      (node (ref "XS1") (pin "1") (pinfunction "VUSB_1") (pintype "passive"))
    )
    (net (code "52") (name "unconnected-(DD1-GPIO.0-Pad14)") (class "Default")
      (node (ref "DD1") (pin "14") (pinfunction "GPIO.0_14") (pintype "passive"))
    )
    (net (code "53") (name "unconnected-(DD1-GPIO.1-Pad13)") (class "Default")
      (node (ref "DD1") (pin "13") (pinfunction "GPIO.1_13") (pintype "passive"))
    )
    (net (code "54") (name "unconnected-(DD1-GPIO.2-Pad12)") (class "Default")
      (node (ref "DD1") (pin "12") (pinfunction "GPIO.2_12") (pintype "passive"))
    )
    (net (code "55") (name "unconnected-(DD1-GPIO.3-Pad11)") (class "Default")
      (node (ref "DD1") (pin "11") (pinfunction "GPIO.3_11") (pintype "passive"))
    )
    (net (code "56") (name "unconnected-(DD1-NC-Pad10)") (class "Default")
      (node (ref "DD1") (pin "10") (pinfunction "NC_10") (pintype "passive"))
    )
    (net (code "57") (name "unconnected-(DD1-SUSPEND-Pad17)") (class "Default")
      (node (ref "DD1") (pin "17") (pinfunction "SUSPEND_17") (pintype "passive"))
    )
    (net (code "58") (name "unconnected-(DD1-~{CTS}-Pad18)") (class "Default")
      (node (ref "DD1") (pin "18") (pinfunction "~{CTS}_18") (pintype "passive"))
    )
    (net (code "59") (name "unconnected-(DD1-~{DCD}-Pad24)") (class "Default")
      (node (ref "DD1") (pin "24") (pinfunction "~{DCD}_24") (pintype "passive"))
    )
    (net (code "60") (name "unconnected-(DD1-~{DSR}-Pad22)") (class "Default")
      (node (ref "DD1") (pin "22") (pinfunction "~{DSR}_22") (pintype "passive"))
    )
    (net (code "61") (name "unconnected-(DD1-~{RI}-Pad1)") (class "Default")
      (node (ref "DD1") (pin "1") (pinfunction "~{RI}_1") (pintype "passive"))
    )
    (net (code "62") (name "unconnected-(DD1-~{SUSPEND}-Pad15)") (class "Default")
      (node (ref "DD1") (pin "15") (pinfunction "~{SUSPEND}_15") (pintype "passive"))
    )
    (net (code "63") (name "unconnected-(DD4-ADC-Pad2)") (class "Default")
      (node (ref "DD4") (pin "2") (pinfunction "ADC_2") (pintype "passive"))
    )
    (net (code "64") (name "unconnected-(DD5-ADC6-Pad19)") (class "Default")
      (node (ref "DD5") (pin "19") (pinfunction "ADC6_19") (pintype "passive"))
    )
    (net (code "65") (name "unconnected-(DD5-ADC7-Pad22)") (class "Default")
      (node (ref "DD5") (pin "22") (pinfunction "ADC7_22") (pintype "passive"))
    )
    (net (code "66") (name "unconnected-(DD5-DAP-Pad33)") (class "Default")
      (node (ref "DD5") (pin "33") (pinfunction "DAP_33") (pintype "passive"))
    )
    (net (code "67") (name "unconnected-(DD5-PB6_(XTAL1)-Pad7)") (class "Default")
      (node (ref "DD5") (pin "7") (pinfunction "PB6_(XTAL1)_7") (pintype "passive"))
    )
    (net (code "68") (name "unconnected-(DD5-PB7_(XTAL2)-Pad8)") (class "Default")
      (node (ref "DD5") (pin "8") (pinfunction "PB7_(XTAL2)_8") (pintype "passive"))
    )
    (net (code "69") (name "unconnected-(DD5-PD7-Pad11)") (class "Default")
      (node (ref "DD5") (pin "11") (pinfunction "PD7_11") (pintype "passive"))
    )
    (net (code "70") (name "unconnected-(DD6-CLKOUT-Pad7)") (class "Default")
      (node (ref "DD6") (pin "7") (pinfunction "CLKOUT_7") (pintype "passive"))
    )
    (net (code "71") (name "unconnected-(DD6-~{INT}-Pad3)") (class "Default")
      (node (ref "DD6") (pin "3") (pinfunction "~{INT}_3") (pintype "passive"))
    )
    (net (code "72") (name "unconnected-(XS1-NC-Pad4)") (class "Default")
      (node (ref "XS1") (pin "4") (pinfunction "NC_4") (pintype "passive"))
    )
    (net (code "73") (name "unconnected-(XS3-IRQ-Pad5)") (class "Default")
      (node (ref "XS3") (pin "5") (pinfunction "IRQ_5") (pintype "passive"))
    )
    (net (code "74") (name "unconnected-(XS5-NC-Pad1)") (class "Default")
      (node (ref "XS5") (pin "1") (pinfunction "NC_1") (pintype "passive"))
    )
    (net (code "75") (name "unconnected-(XS5-NC-Pad8)") (class "Default")
      (node (ref "XS5") (pin "8") (pinfunction "NC_8") (pintype "passive"))
    )
  )
)
